# Shema.net
KiCad netlist of a schematic drawn in EAGLE
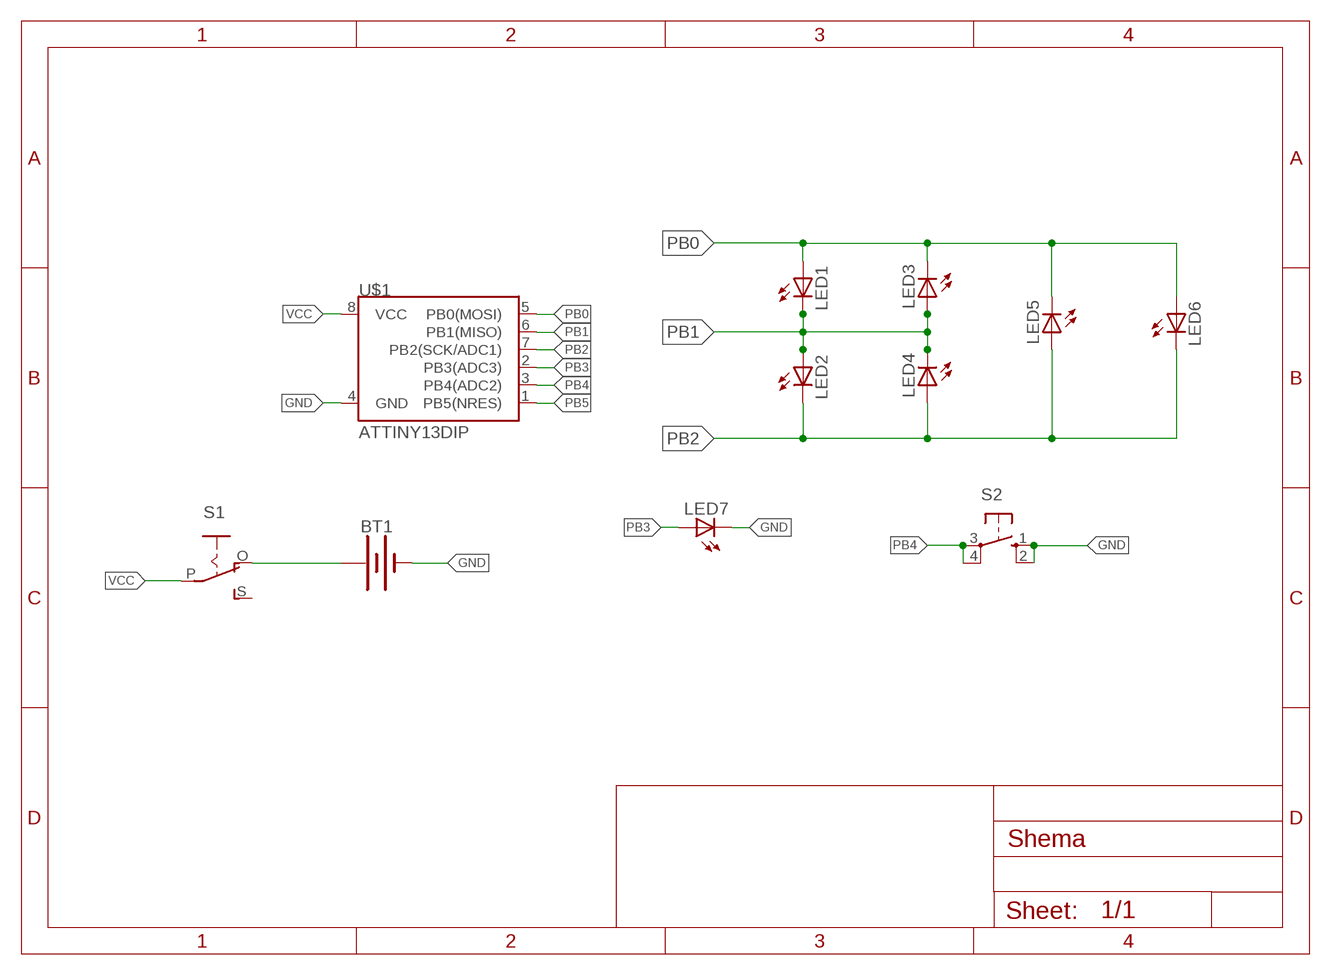
[diagram p0: schematic, sheet 1]

(export (version "E")
  (design (tool "Eeschema 10.0.6"))
  (components
    (comp (ref "BT1")
      (value "BATTERY-20MM_PTH")
      (footprint "eagle-import:BATTCOM_20MM_PTH")
      (libsource (lib "eagle-import") (part "BATTERY-20MM_PTH"))
    )
    (comp (ref "LED1")
      (value "LED5MM")
      (footprint "eagle-import:LED5MM")
      (libsource (lib "eagle-import") (part "LED5MM"))
    )
    (comp (ref "LED2")
      (value "LED5MM")
      (footprint "eagle-import:LED5MM")
      (libsource (lib "eagle-import") (part "LED5MM"))
    )
    (comp (ref "LED3")
      (value "LED5MM")
      (footprint "eagle-import:LED5MM")
      (libsource (lib "eagle-import") (part "LED5MM"))
    )
    (comp (ref "LED4")
      (value "LED5MM")
      (footprint "eagle-import:LED5MM")
      (libsource (lib "eagle-import") (part "LED5MM"))
    )
    (comp (ref "LED5")
      (value "LED5MM")
      (footprint "eagle-import:LED5MM")
      (libsource (lib "eagle-import") (part "LED5MM"))
    )
    (comp (ref "LED6")
      (value "LED5MM")
      (footprint "eagle-import:LED5MM")
      (libsource (lib "eagle-import") (part "LED5MM"))
    )
    (comp (ref "LED7")
      (value "LED5MM")
      (footprint "eagle-import:LED5MM")
      (libsource (lib "eagle-import") (part "LED5MM"))
    )
    (comp (ref "S1")
      (value "EG1218S")
      (footprint "eagle-import:EG1218")
      (libsource (lib "eagle-import") (part "EG1218S"))
    )
    (comp (ref "S2")
      (value "40-XX")
      (footprint "eagle-import:B3F-40XX")
      (fields (field (name "MF") "OMRON COMPONENTS USA") (field (name "MPN") "B3F-4000"))
      (libsource (lib "eagle-import") (part "40-XX"))
    )
    (comp (ref "U$1")
      (value "ATTINY13DIP")
      (footprint "eagle-import:DIP08_MCU")
      (libsource (lib "eagle-import") (part "ATTINY13DIP"))
    )
  )
  (nets
    (net (code "1") (name "GND") (class "Default")
      (node (ref "BT1") (pin "2") (pinfunction "-_2") (pintype "power_in"))
      (node (ref "LED7") (pin "K") (pinfunction "C_K") (pintype "passive"))
      (node (ref "S2") (pin "1") (pinfunction "S_1") (pintype "passive"))
      (node (ref "S2") (pin "2") (pinfunction "S1_2") (pintype "passive"))
      (node (ref "U$1") (pin "4") (pinfunction "GND_4") (pintype "bidirectional"))
    )
    (net (code "2") (name "Net-(BT1-+)") (class "Default")
      (node (ref "BT1") (pin "1") (pinfunction "+_1") (pintype "power_in"))
      (node (ref "S1") (pin "O") (pinfunction "O_O") (pintype "passive"))
    )
    (net (code "3") (name "PB0") (class "Default")
      (node (ref "LED1") (pin "A") (pinfunction "A_A") (pintype "passive"))
      (node (ref "LED3") (pin "K") (pinfunction "C_K") (pintype "passive"))
      (node (ref "LED5") (pin "K") (pinfunction "C_K") (pintype "passive"))
      (node (ref "LED6") (pin "A") (pinfunction "A_A") (pintype "passive"))
      (node (ref "U$1") (pin "5") (pinfunction "PB0(MOSI)_5") (pintype "bidirectional"))
    )
    (net (code "4") (name "PB1") (class "Default")
      (node (ref "LED1") (pin "K") (pinfunction "C_K") (pintype "passive"))
      (node (ref "LED2") (pin "A") (pinfunction "A_A") (pintype "passive"))
      (node (ref "LED3") (pin "A") (pinfunction "A_A") (pintype "passive"))
      (node (ref "LED4") (pin "K") (pinfunction "C_K") (pintype "passive"))
      (node (ref "U$1") (pin "6") (pinfunction "PB1(MISO)_6") (pintype "bidirectional"))
    )
    (net (code "5") (name "PB2") (class "Default")
      (node (ref "LED2") (pin "K") (pinfunction "C_K") (pintype "passive"))
      (node (ref "LED4") (pin "A") (pinfunction "A_A") (pintype "passive"))
      (node (ref "LED5") (pin "A") (pinfunction "A_A") (pintype "passive"))
      (node (ref "LED6") (pin "K") (pinfunction "C_K") (pintype "passive"))
      (node (ref "U$1") (pin "7") (pinfunction "PB2(SCK/ADC1)_7") (pintype "bidirectional"))
    )
    (net (code "6") (name "PB3") (class "Default")
      (node (ref "LED7") (pin "A") (pinfunction "A_A") (pintype "passive"))
      (node (ref "U$1") (pin "2") (pinfunction "PB3(ADC3)_2") (pintype "bidirectional"))
    )
    (net (code "7") (name "PB4") (class "Default")
      (node (ref "S2") (pin "3") (pinfunction "P_3") (pintype "passive"))
      (node (ref "S2") (pin "4") (pinfunction "P1_4") (pintype "passive"))
      (node (ref "U$1") (pin "3") (pinfunction "PB4(ADC2)_3") (pintype "bidirectional"))
    )
    (net (code "8") (name "PB5") (class "Default")
      (node (ref "U$1") (pin "1") (pinfunction "PB5(NRES)_1") (pintype "bidirectional"))
    )
    (net (code "9") (name "VCC") (class "Default")
      (node (ref "S1") (pin "P") (pinfunction "P_P") (pintype "passive"))
      (node (ref "U$1") (pin "8") (pinfunction "VCC_8") (pintype "bidirectional"))
    )
    (net (code "10") (name "unconnected-(S1-PadS)") (class "Default")
      (node (ref "S1") (pin "S") (pinfunction "S_S") (pintype "passive"))
    )
  )
)
